# AA8513.net
KiCad netlist of a schematic drawn in Altium Designer
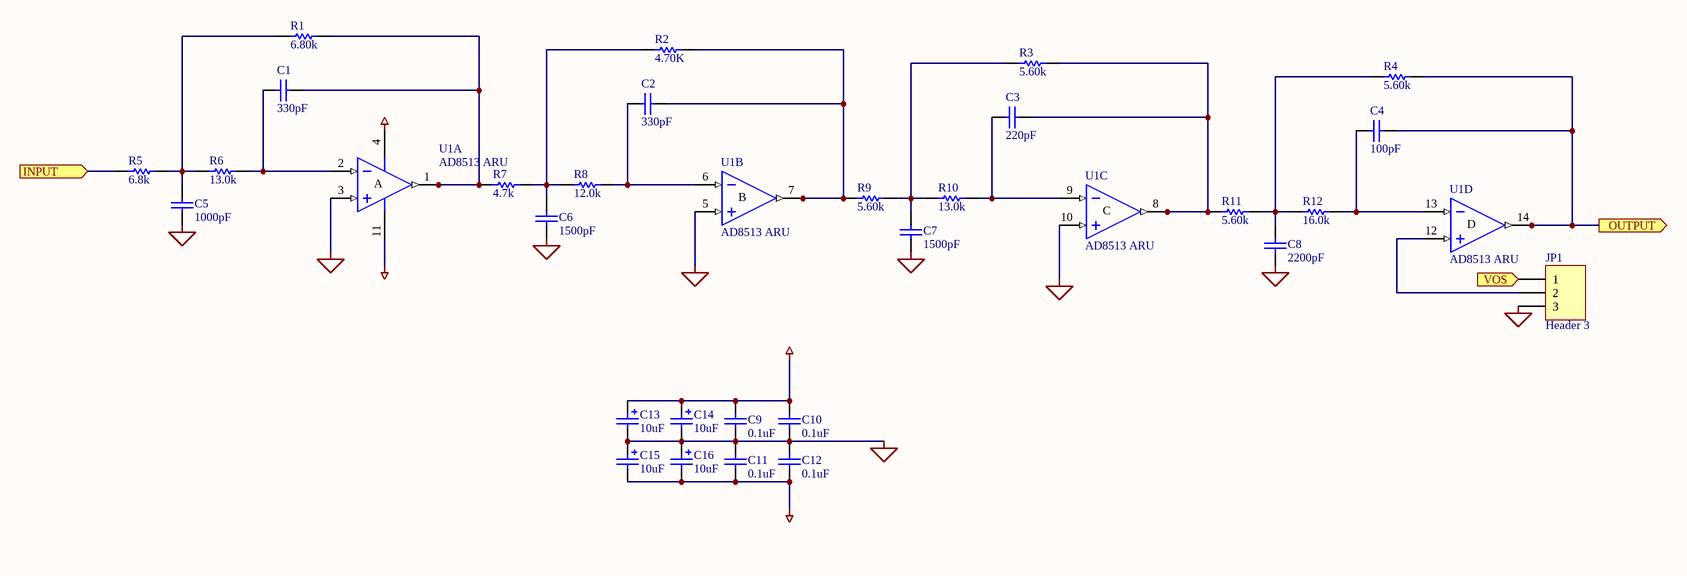
[diagram p0: AA8513.SCHDOC]

(export (version "E")
  (design (tool "Eeschema 10.0.6"))
  (components
    (comp (ref "C1")
      (value "Cap")
      (footprint "CC3216-1206")
      (description "Capacitor")
      (fields
        (field (name "MANUFACTURER") "Generic Components")
        (field (name "ALTIUM_VALUE") "330pF")
        (field (name "PUBLISHER") "Altium Limited")
      )
      (libsource (lib "Miscellaneous Devices") (part "Cap"))
    )
    (comp (ref "C2")
      (value "Cap")
      (footprint "CC3216-1206")
      (description "Capacitor")
      (fields
        (field (name "MANUFACTURER") "Generic Components")
        (field (name "ALTIUM_VALUE") "330pF")
        (field (name "PUBLISHER") "Altium Limited")
      )
      (libsource (lib "Miscellaneous Devices") (part "Cap"))
    )
    (comp (ref "C3")
      (value "Cap")
      (footprint "CC3216-1206")
      (description "Capacitor")
      (fields
        (field (name "MANUFACTURER") "Generic Components")
        (field (name "ALTIUM_VALUE") "220pF")
        (field (name "PUBLISHER") "Altium Limited")
      )
      (libsource (lib "Miscellaneous Devices") (part "Cap"))
    )
    (comp (ref "C4")
      (value "Cap")
      (footprint "CC3216-1206")
      (description "Capacitor")
      (fields
        (field (name "MANUFACTURER") "Generic Components")
        (field (name "ALTIUM_VALUE") "100pF")
        (field (name "PUBLISHER") "Altium Limited")
      )
      (libsource (lib "Miscellaneous Devices") (part "Cap"))
    )
    (comp (ref "C5")
      (value "Cap")
      (footprint "CC3216-1206")
      (description "Capacitor")
      (fields
        (field (name "MANUFACTURER") "Generic Components")
        (field (name "ALTIUM_VALUE") "1000pF")
        (field (name "PUBLISHER") "Altium Limited")
      )
      (libsource (lib "Miscellaneous Devices") (part "Cap"))
    )
    (comp (ref "C6")
      (value "Cap")
      (footprint "CC3216-1206")
      (description "Capacitor")
      (fields
        (field (name "MANUFACTURER") "Generic Components")
        (field (name "ALTIUM_VALUE") "1500pF")
        (field (name "PUBLISHER") "Altium Limited")
      )
      (libsource (lib "Miscellaneous Devices") (part "Cap"))
    )
    (comp (ref "C7")
      (value "Cap")
      (footprint "CC3216-1206")
      (description "Capacitor")
      (fields
        (field (name "MANUFACTURER") "Generic Components")
        (field (name "ALTIUM_VALUE") "1500pF")
        (field (name "PUBLISHER") "Altium Limited")
      )
      (libsource (lib "Miscellaneous Devices") (part "Cap"))
    )
    (comp (ref "C8")
      (value "Cap")
      (footprint "CC3216-1206")
      (description "Capacitor")
      (fields
        (field (name "MANUFACTURER") "Generic Components")
        (field (name "ALTIUM_VALUE") "2200pF")
        (field (name "PUBLISHER") "Altium Limited")
      )
      (libsource (lib "Miscellaneous Devices") (part "Cap"))
    )
    (comp (ref "C9")
      (value "Cap")
      (footprint "CC1608-0603")
      (description "Capacitor")
      (fields
        (field (name "MANUFACTURER") "Generic Components")
        (field (name "ALTIUM_VALUE") "0.1uF")
        (field (name "PUBLISHER") "Altium Limited")
      )
      (libsource (lib "Miscellaneous Devices") (part "Cap"))
    )
    (comp (ref "C10")
      (value "Cap")
      (footprint "CC1608-0603")
      (description "Capacitor")
      (fields
        (field (name "MANUFACTURER") "Generic Components")
        (field (name "ALTIUM_VALUE") "0.1uF")
        (field (name "PUBLISHER") "Altium Limited")
      )
      (libsource (lib "Miscellaneous Devices") (part "Cap"))
    )
    (comp (ref "C11")
      (value "Cap")
      (footprint "CC1608-0603")
      (description "Capacitor")
      (fields
        (field (name "MANUFACTURER") "Generic Components")
        (field (name "ALTIUM_VALUE") "0.1uF")
        (field (name "PUBLISHER") "Altium Limited")
      )
      (libsource (lib "Miscellaneous Devices") (part "Cap"))
    )
    (comp (ref "C12")
      (value "Cap")
      (footprint "CC1608-0603")
      (description "Capacitor")
      (fields
        (field (name "MANUFACTURER") "Generic Components")
        (field (name "ALTIUM_VALUE") "0.1uF")
        (field (name "PUBLISHER") "Altium Limited")
      )
      (libsource (lib "Miscellaneous Devices") (part "Cap"))
    )
    (comp (ref "C13")
      (value "Cap Pol1")
      (footprint "TC7360-2924")
      (description "Polarized Capacitor (Radial)")
      (fields
        (field (name "MANUFACTURER") "Generic Components")
        (field (name "ALTIUM_VALUE") "10uF")
        (field (name "PUBLISHER") "Altium Limited")
      )
      (libsource (lib "Miscellaneous Devices") (part "Cap Pol1"))
    )
    (comp (ref "C14")
      (value "Cap Pol1")
      (footprint "TC7360-2924")
      (description "Polarized Capacitor (Radial)")
      (fields
        (field (name "MANUFACTURER") "Generic Components")
        (field (name "ALTIUM_VALUE") "10uF")
        (field (name "PUBLISHER") "Altium Limited")
      )
      (libsource (lib "Miscellaneous Devices") (part "Cap Pol1"))
    )
    (comp (ref "C15")
      (value "Cap Pol1")
      (footprint "TC7360-2924")
      (description "Polarized Capacitor (Radial)")
      (fields
        (field (name "MANUFACTURER") "Generic Components")
        (field (name "ALTIUM_VALUE") "10uF")
        (field (name "PUBLISHER") "Altium Limited")
      )
      (libsource (lib "Miscellaneous Devices") (part "Cap Pol1"))
    )
    (comp (ref "C16")
      (value "Cap Pol1")
      (footprint "TC7360-2924")
      (description "Polarized Capacitor (Radial)")
      (fields
        (field (name "MANUFACTURER") "Generic Components")
        (field (name "ALTIUM_VALUE") "10uF")
        (field (name "PUBLISHER") "Altium Limited")
      )
      (libsource (lib "Miscellaneous Devices") (part "Cap Pol1"))
    )
    (comp (ref "JP1")
      (value "Header 3")
      (footprint "HDR1X3")
      (description "Header, 3-Pin")
      (fields (field (name "MANUFACTURER") "Generic Components") (field (name "PUBLISHER") "Altium Limited"))
      (libsource (lib "Miscellaneous Connectors") (part "Header 3"))
    )
    (comp (ref "R1")
      (value "Res1")
      (footprint "CC2012-0805")
      (description "Resistor")
      (fields
        (field (name "MANUFACTURER") "Generic Components")
        (field (name "ALTIUM_VALUE") "6.80k")
        (field (name "PUBLISHER") "Altium Limited")
      )
      (libsource (lib "Miscellaneous Devices") (part "Res1"))
    )
    (comp (ref "R2")
      (value "Res1")
      (footprint "CC2012-0805")
      (description "Resistor")
      (fields
        (field (name "MANUFACTURER") "Generic Components")
        (field (name "ALTIUM_VALUE") "4.70K")
        (field (name "PUBLISHER") "Altium Limited")
      )
      (libsource (lib "Miscellaneous Devices") (part "Res1"))
    )
    (comp (ref "R3")
      (value "Res1")
      (footprint "CC2012-0805")
      (description "Resistor")
      (fields
        (field (name "MANUFACTURER") "Generic Components")
        (field (name "ALTIUM_VALUE") "5.60k")
        (field (name "PUBLISHER") "Altium Limited")
      )
      (libsource (lib "Miscellaneous Devices") (part "Res1"))
    )
    (comp (ref "R4")
      (value "Res1")
      (footprint "CC2012-0805")
      (description "Resistor")
      (fields
        (field (name "MANUFACTURER") "Generic Components")
        (field (name "ALTIUM_VALUE") "5.60k")
        (field (name "PUBLISHER") "Altium Limited")
      )
      (libsource (lib "Miscellaneous Devices") (part "Res1"))
    )
    (comp (ref "R5")
      (value "Res1")
      (footprint "CC2012-0805")
      (description "Resistor")
      (fields
        (field (name "MANUFACTURER") "Generic Components")
        (field (name "ALTIUM_VALUE") "6.8k")
        (field (name "PUBLISHER") "Altium Limited")
      )
      (libsource (lib "Miscellaneous Devices") (part "Res1"))
    )
    (comp (ref "R6")
      (value "Res1")
      (footprint "CC2012-0805")
      (description "Resistor")
      (fields
        (field (name "MANUFACTURER") "Generic Components")
        (field (name "ALTIUM_VALUE") "13.0k")
        (field (name "PUBLISHER") "Altium Limited")
      )
      (libsource (lib "Miscellaneous Devices") (part "Res1"))
    )
    (comp (ref "R7")
      (value "Res1")
      (footprint "CC2012-0805")
      (description "Resistor")
      (fields
        (field (name "MANUFACTURER") "Generic Components")
        (field (name "ALTIUM_VALUE") "4.7k")
        (field (name "PUBLISHER") "Altium Limited")
      )
      (libsource (lib "Miscellaneous Devices") (part "Res1"))
    )
    (comp (ref "R8")
      (value "Res1")
      (footprint "CC2012-0805")
      (description "Resistor")
      (fields
        (field (name "MANUFACTURER") "Generic Components")
        (field (name "ALTIUM_VALUE") "12.0k")
        (field (name "PUBLISHER") "Altium Limited")
      )
      (libsource (lib "Miscellaneous Devices") (part "Res1"))
    )
    (comp (ref "R9")
      (value "Res1")
      (footprint "CC2012-0805")
      (description "Resistor")
      (fields
        (field (name "MANUFACTURER") "Generic Components")
        (field (name "ALTIUM_VALUE") "5.60k")
        (field (name "PUBLISHER") "Altium Limited")
      )
      (libsource (lib "Miscellaneous Devices") (part "Res1"))
    )
    (comp (ref "R10")
      (value "Res1")
      (footprint "CC2012-0805")
      (description "Resistor")
      (fields
        (field (name "MANUFACTURER") "Generic Components")
        (field (name "ALTIUM_VALUE") "13.0k")
        (field (name "PUBLISHER") "Altium Limited")
      )
      (libsource (lib "Miscellaneous Devices") (part "Res1"))
    )
    (comp (ref "R11")
      (value "Res1")
      (footprint "CC2012-0805")
      (description "Resistor")
      (fields
        (field (name "MANUFACTURER") "Generic Components")
        (field (name "ALTIUM_VALUE") "5.60k")
        (field (name "PUBLISHER") "Altium Limited")
      )
      (libsource (lib "Miscellaneous Devices") (part "Res1"))
    )
    (comp (ref "R12")
      (value "Res1")
      (footprint "CC2012-0805")
      (description "Resistor")
      (fields
        (field (name "MANUFACTURER") "Generic Components")
        (field (name "ALTIUM_VALUE") "16.0k")
        (field (name "PUBLISHER") "Altium Limited")
      )
      (libsource (lib "Miscellaneous Devices") (part "Res1"))
    )
    (comp (ref "U1")
      (value "AD8513 ARU")
      (footprint "TSSO5X6-G14/X.3")
      (description "low-noise JFET quad OA")
      (libsource (lib "My devices") (part "AD8513ARU"))
    )
  )
  (nets
    (net (code "1") (name "/INPUT") (class "Default")
      (node (ref "R5") (pin "1") (pinfunction "1_1") (pintype "passive"))
    )
    (net (code "2") (name "/OUTPUT") (class "Default")
      (node (ref "C4") (pin "1") (pinfunction "1_1") (pintype "passive"))
      (node (ref "R4") (pin "1") (pinfunction "1_1") (pintype "passive"))
      (node (ref "U1") (pin "14") (pinfunction "OUTD_14") (pintype "output"))
    )
    (net (code "3") (name "/VOS") (class "Default")
      (node (ref "JP1") (pin "1") (pinfunction "1_1") (pintype "passive"))
    )
    (net (code "4") (name "AVDD") (class "Default")
      (node (ref "C10") (pin "2") (pinfunction "2_2") (pintype "passive"))
      (node (ref "C13") (pin "1") (pinfunction "1_1") (pintype "passive"))
      (node (ref "C14") (pin "1") (pinfunction "1_1") (pintype "passive"))
      (node (ref "C9") (pin "2") (pinfunction "2_2") (pintype "passive"))
      (node (ref "U1") (pin "4") (pinfunction "V+_4") (pintype "power_in"))
    )
    (net (code "5") (name "AVSS") (class "Default")
      (node (ref "C11") (pin "1") (pinfunction "1_1") (pintype "passive"))
      (node (ref "C12") (pin "1") (pinfunction "1_1") (pintype "passive"))
      (node (ref "C15") (pin "2") (pinfunction "2_2") (pintype "passive"))
      (node (ref "C16") (pin "2") (pinfunction "2_2") (pintype "passive"))
      (node (ref "U1") (pin "11") (pinfunction "V-_11") (pintype "power_in"))
    )
    (net (code "6") (name "GND") (class "Default")
      (node (ref "C10") (pin "1") (pinfunction "1_1") (pintype "passive"))
      (node (ref "C11") (pin "2") (pinfunction "2_2") (pintype "passive"))
      (node (ref "C12") (pin "2") (pinfunction "2_2") (pintype "passive"))
      (node (ref "C13") (pin "2") (pinfunction "2_2") (pintype "passive"))
      (node (ref "C14") (pin "2") (pinfunction "2_2") (pintype "passive"))
      (node (ref "C15") (pin "1") (pinfunction "1_1") (pintype "passive"))
      (node (ref "C16") (pin "1") (pinfunction "1_1") (pintype "passive"))
      (node (ref "C5") (pin "1") (pinfunction "1_1") (pintype "passive"))
      (node (ref "C6") (pin "1") (pinfunction "1_1") (pintype "passive"))
      (node (ref "C7") (pin "1") (pinfunction "1_1") (pintype "passive"))
      (node (ref "C8") (pin "1") (pinfunction "1_1") (pintype "passive"))
      (node (ref "C9") (pin "1") (pinfunction "1_1") (pintype "passive"))
      (node (ref "JP1") (pin "3") (pinfunction "3_3") (pintype "passive"))
      (node (ref "U1") (pin "10") (pinfunction "IN+C_10") (pintype "input"))
      (node (ref "U1") (pin "3") (pinfunction "IN+A_3") (pintype "input"))
      (node (ref "U1") (pin "5") (pinfunction "IN+B_5") (pintype "input"))
    )
    (net (code "7") (name "Net-(C5-Pad2)") (class "Default")
      (node (ref "C5") (pin "2") (pinfunction "2_2") (pintype "passive"))
      (node (ref "R1") (pin "2") (pinfunction "2_2") (pintype "passive"))
      (node (ref "R5") (pin "2") (pinfunction "2_2") (pintype "passive"))
      (node (ref "R6") (pin "1") (pinfunction "1_1") (pintype "passive"))
    )
    (net (code "8") (name "Net-(C6-Pad2)") (class "Default")
      (node (ref "C6") (pin "2") (pinfunction "2_2") (pintype "passive"))
      (node (ref "R2") (pin "2") (pinfunction "2_2") (pintype "passive"))
      (node (ref "R7") (pin "2") (pinfunction "2_2") (pintype "passive"))
      (node (ref "R8") (pin "1") (pinfunction "1_1") (pintype "passive"))
    )
    (net (code "9") (name "Net-(C7-Pad2)") (class "Default")
      (node (ref "C7") (pin "2") (pinfunction "2_2") (pintype "passive"))
      (node (ref "R10") (pin "1") (pinfunction "1_1") (pintype "passive"))
      (node (ref "R3") (pin "2") (pinfunction "2_2") (pintype "passive"))
      (node (ref "R9") (pin "2") (pinfunction "2_2") (pintype "passive"))
    )
    (net (code "10") (name "Net-(C8-Pad2)") (class "Default")
      (node (ref "C8") (pin "2") (pinfunction "2_2") (pintype "passive"))
      (node (ref "R11") (pin "2") (pinfunction "2_2") (pintype "passive"))
      (node (ref "R12") (pin "1") (pinfunction "1_1") (pintype "passive"))
      (node (ref "R4") (pin "2") (pinfunction "2_2") (pintype "passive"))
    )
    (net (code "11") (name "Net-(U1A-IN-A)") (class "Default")
      (node (ref "C1") (pin "2") (pinfunction "2_2") (pintype "passive"))
      (node (ref "R6") (pin "2") (pinfunction "2_2") (pintype "passive"))
      (node (ref "U1") (pin "2") (pinfunction "IN-A_2") (pintype "input"))
    )
    (net (code "12") (name "Net-(U1A-OUTA)") (class "Default")
      (node (ref "C1") (pin "1") (pinfunction "1_1") (pintype "passive"))
      (node (ref "R1") (pin "1") (pinfunction "1_1") (pintype "passive"))
      (node (ref "R7") (pin "1") (pinfunction "1_1") (pintype "passive"))
      (node (ref "U1") (pin "1") (pinfunction "OUTA_1") (pintype "output"))
    )
    (net (code "13") (name "Net-(U1B-IN-B)") (class "Default")
      (node (ref "C2") (pin "2") (pinfunction "2_2") (pintype "passive"))
      (node (ref "R8") (pin "2") (pinfunction "2_2") (pintype "passive"))
      (node (ref "U1") (pin "6") (pinfunction "IN-B_6") (pintype "input"))
    )
    (net (code "14") (name "Net-(U1B-OUTB)") (class "Default")
      (node (ref "C2") (pin "1") (pinfunction "1_1") (pintype "passive"))
      (node (ref "R2") (pin "1") (pinfunction "1_1") (pintype "passive"))
      (node (ref "R9") (pin "1") (pinfunction "1_1") (pintype "passive"))
      (node (ref "U1") (pin "7") (pinfunction "OUTB_7") (pintype "output"))
    )
    (net (code "15") (name "Net-(U1C-IN-C)") (class "Default")
      (node (ref "C3") (pin "2") (pinfunction "2_2") (pintype "passive"))
      (node (ref "R10") (pin "2") (pinfunction "2_2") (pintype "passive"))
      (node (ref "U1") (pin "9") (pinfunction "IN-C_9") (pintype "input"))
    )
    (net (code "16") (name "Net-(U1C-OUTC)") (class "Default")
      (node (ref "C3") (pin "1") (pinfunction "1_1") (pintype "passive"))
      (node (ref "R11") (pin "1") (pinfunction "1_1") (pintype "passive"))
      (node (ref "R3") (pin "1") (pinfunction "1_1") (pintype "passive"))
      (node (ref "U1") (pin "8") (pinfunction "OUTC_8") (pintype "output"))
    )
    (net (code "17") (name "Net-(U1D-IN+D)") (class "Default")
      (node (ref "JP1") (pin "2") (pinfunction "2_2") (pintype "passive"))
      (node (ref "U1") (pin "12") (pinfunction "IN+D_12") (pintype "input"))
    )
    (net (code "18") (name "Net-(U1D-IN-D)") (class "Default")
      (node (ref "C4") (pin "2") (pinfunction "2_2") (pintype "passive"))
      (node (ref "R12") (pin "2") (pinfunction "2_2") (pintype "passive"))
      (node (ref "U1") (pin "13") (pinfunction "IN-D_13") (pintype "input"))
    )
  )
)
